# logic_7408_v1_1.net
KiCad netlist of a schematic drawn in EAGLE
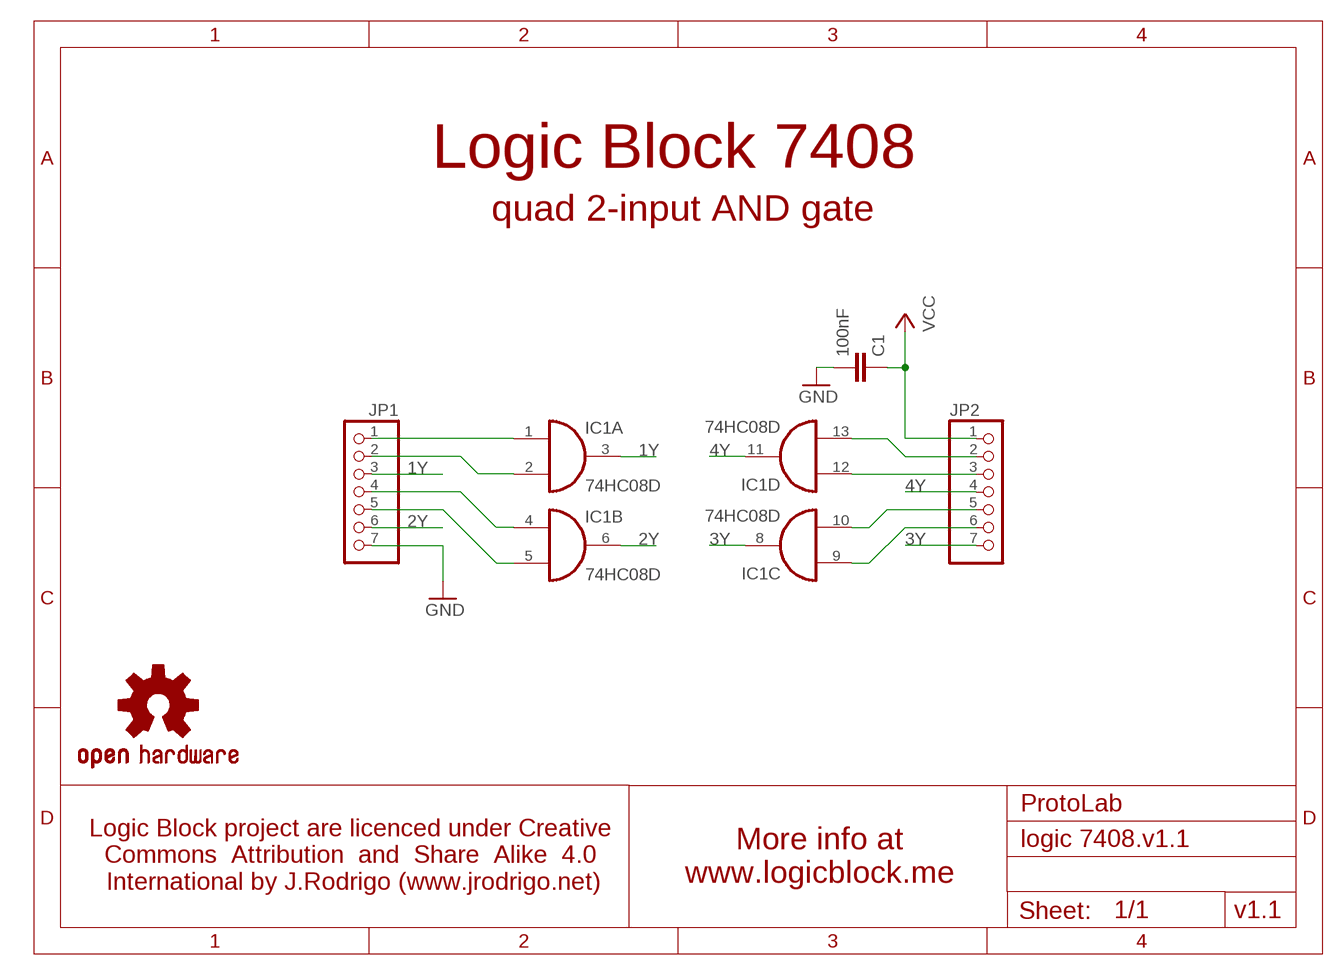
[diagram p0: schematic, sheet 1]

(export (version "E")
  (design (tool "Eeschema 10.0.6"))
  (components
    (comp (ref "C1")
      (value "100nF")
      (footprint "eagle-import:C0805K")
      (libsource (lib "eagle-import") (part "C-EUC0805K"))
    )
    (comp (ref "IC1")
      (value "74HC08D")
      (footprint "eagle-import:SO14")
      (libsource (lib "eagle-import") (part "7408DHC"))
    )
    (comp (ref "JP1")
      (value "CON_1X7CLEANBIG")
      (footprint "eagle-import:CON_1X07-CLEANBIG")
      (libsource (lib "eagle-import") (part "CON_1X7CLEANBIG"))
    )
    (comp (ref "JP2")
      (value "CON_1X7CLEANBIG")
      (footprint "eagle-import:CON_1X07-CLEANBIG")
      (libsource (lib "eagle-import") (part "CON_1X7CLEANBIG"))
    )
    (comp (ref "U$1")
      (value "OSHW-LOGOS-LAYER230")
      (footprint "eagle-import:OSHW-LOGO-S_LAYER230")
      (libsource (lib "eagle-import") (part "OSHW-LOGOS-LAYER230"))
    )
  )
  (nets
    (net (code "1") (name "/1Y") (class "Default")
      (node (ref "IC1") (pin "3") (pinfunction "O_3") (pintype "output"))
      (node (ref "JP1") (pin "3") (pinfunction "3_3") (pintype "passive"))
    )
    (net (code "2") (name "/2Y") (class "Default")
      (node (ref "IC1") (pin "6") (pinfunction "O_6") (pintype "output"))
      (node (ref "JP1") (pin "6") (pinfunction "6_6") (pintype "passive"))
    )
    (net (code "3") (name "/3Y") (class "Default")
      (node (ref "IC1") (pin "8") (pinfunction "O_8") (pintype "output"))
      (node (ref "JP2") (pin "7") (pinfunction "7_7") (pintype "passive"))
    )
    (net (code "4") (name "/4Y") (class "Default")
      (node (ref "IC1") (pin "11") (pinfunction "O_11") (pintype "output"))
      (node (ref "JP2") (pin "4") (pinfunction "4_4") (pintype "passive"))
    )
    (net (code "5") (name "GND") (class "Default")
      (node (ref "C1") (pin "2") (pinfunction "2_2") (pintype "passive"))
      (node (ref "JP1") (pin "7") (pinfunction "7_7") (pintype "passive"))
    )
    (net (code "6") (name "Net-(IC1A-I0)") (class "Default")
      (node (ref "IC1") (pin "1") (pinfunction "I0_1") (pintype "input"))
      (node (ref "JP1") (pin "1") (pinfunction "1_1") (pintype "passive"))
    )
    (net (code "7") (name "Net-(IC1A-I1)") (class "Default")
      (node (ref "IC1") (pin "2") (pinfunction "I1_2") (pintype "input"))
      (node (ref "JP1") (pin "2") (pinfunction "2_2") (pintype "passive"))
    )
    (net (code "8") (name "Net-(IC1B-I0)") (class "Default")
      (node (ref "IC1") (pin "4") (pinfunction "I0_4") (pintype "input"))
      (node (ref "JP1") (pin "4") (pinfunction "4_4") (pintype "passive"))
    )
    (net (code "9") (name "Net-(IC1B-I1)") (class "Default")
      (node (ref "IC1") (pin "5") (pinfunction "I1_5") (pintype "input"))
      (node (ref "JP1") (pin "5") (pinfunction "5_5") (pintype "passive"))
    )
    (net (code "10") (name "Net-(IC1C-I0)") (class "Default")
      (node (ref "IC1") (pin "9") (pinfunction "I0_9") (pintype "input"))
      (node (ref "JP2") (pin "6") (pinfunction "6_6") (pintype "passive"))
    )
    (net (code "11") (name "Net-(IC1C-I1)") (class "Default")
      (node (ref "IC1") (pin "10") (pinfunction "I1_10") (pintype "input"))
      (node (ref "JP2") (pin "5") (pinfunction "5_5") (pintype "passive"))
    )
    (net (code "12") (name "Net-(IC1D-I0)") (class "Default")
      (node (ref "IC1") (pin "12") (pinfunction "I0_12") (pintype "input"))
      (node (ref "JP2") (pin "3") (pinfunction "3_3") (pintype "passive"))
    )
    (net (code "13") (name "Net-(IC1D-I1)") (class "Default")
      (node (ref "IC1") (pin "13") (pinfunction "I1_13") (pintype "input"))
      (node (ref "JP2") (pin "2") (pinfunction "2_2") (pintype "passive"))
    )
    (net (code "14") (name "VCC") (class "Default")
      (node (ref "C1") (pin "1") (pinfunction "1_1") (pintype "passive"))
      (node (ref "JP2") (pin "1") (pinfunction "1_1") (pintype "passive"))
    )
  )
)
